# STM32_demo.net
KiCad netlist of a schematic drawn in Altium Designer
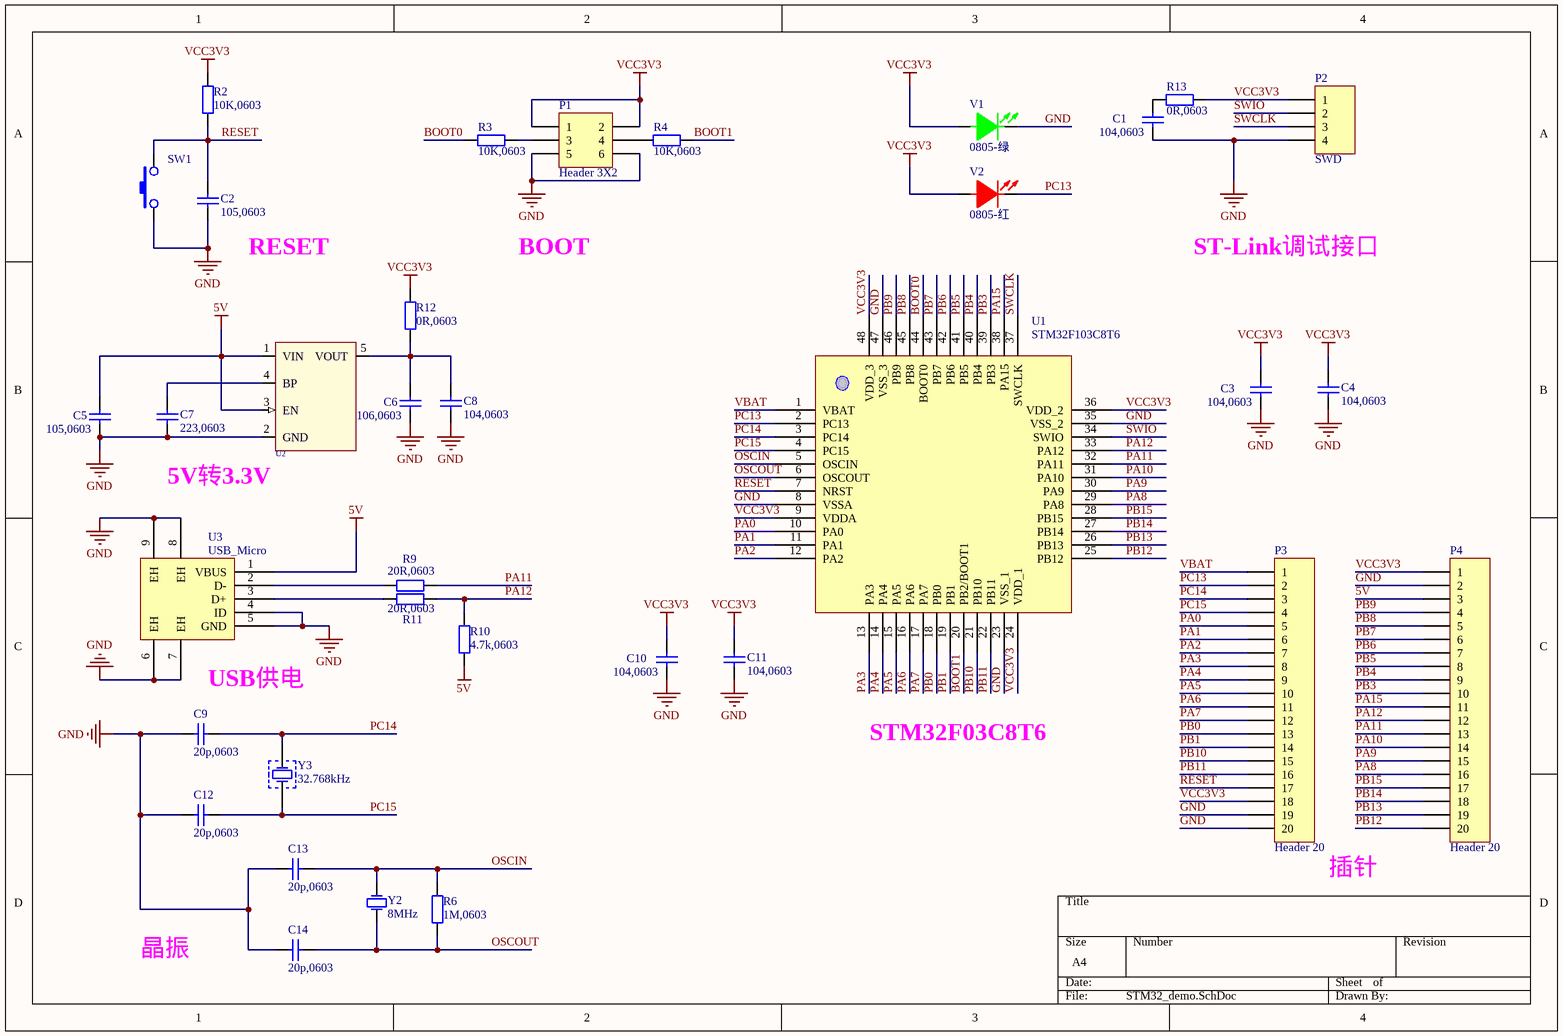
[diagram p0: STM32_demo.SchDoc]

(export (version "E")
  (design (tool "Eeschema 10.0.6"))
  (components
    (comp (ref "C1")
      (value "104,0603")
      (footprint "C0603")
      (description "Capacitor")
      (fields (field (name "PUBLISHER") "Altium Limited"))
      (libsource (lib "STM32F103C8T6") (part "Cap"))
    )
    (comp (ref "C2")
      (value "105,0603")
      (footprint "C0603")
      (description "Capacitor")
      (fields (field (name "PUBLISHER") "Altium Limited"))
      (libsource (lib "STM32F103C8T6") (part "Cap"))
    )
    (comp (ref "C3")
      (value "104,0603")
      (footprint "C0603")
      (description "Capacitor")
      (fields (field (name "PUBLISHER") "Altium Limited"))
      (libsource (lib "STM32F103C8T6") (part "Cap"))
    )
    (comp (ref "C4")
      (value "104,0603")
      (footprint "C0603")
      (description "Capacitor")
      (fields (field (name "PUBLISHER") "Altium Limited"))
      (libsource (lib "STM32F103C8T6") (part "Cap"))
    )
    (comp (ref "C5")
      (value "105,0603")
      (footprint "C0603")
      (description "Capacitor")
      (fields (field (name "PUBLISHER") "Altium Limited"))
      (libsource (lib "STM32F103C8T6") (part "Cap"))
    )
    (comp (ref "C6")
      (value "106,0603")
      (footprint "C0603")
      (description "Capacitor")
      (fields (field (name "PUBLISHER") "Altium Limited"))
      (libsource (lib "STM32F103C8T6") (part "Cap"))
    )
    (comp (ref "C7")
      (value "223,0603")
      (footprint "C0603")
      (description "Capacitor")
      (fields (field (name "PUBLISHER") "Altium Limited"))
      (libsource (lib "STM32F103C8T6") (part "Cap"))
    )
    (comp (ref "C8")
      (value "104,0603")
      (footprint "C0603")
      (description "Capacitor")
      (fields (field (name "PUBLISHER") "Altium Limited"))
      (libsource (lib "STM32F103C8T6") (part "Cap"))
    )
    (comp (ref "C9")
      (value "20p,0603")
      (footprint "C0603")
      (description "Capacitor")
      (fields (field (name "PUBLISHER") "Altium Limited"))
      (libsource (lib "STM32F103C8T6") (part "Cap"))
    )
    (comp (ref "C10")
      (value "104,0603")
      (footprint "C0603")
      (description "Capacitor")
      (fields (field (name "PUBLISHER") "Altium Limited"))
      (libsource (lib "STM32F103C8T6") (part "Cap"))
    )
    (comp (ref "C11")
      (value "104,0603")
      (footprint "C0603")
      (description "Capacitor")
      (fields (field (name "PUBLISHER") "Altium Limited"))
      (libsource (lib "STM32F103C8T6") (part "Cap"))
    )
    (comp (ref "C12")
      (value "20p,0603")
      (footprint "C0603")
      (description "Capacitor")
      (fields (field (name "PUBLISHER") "Altium Limited"))
      (libsource (lib "STM32F103C8T6") (part "Cap"))
    )
    (comp (ref "C13")
      (value "20p,0603")
      (footprint "C0603")
      (description "Capacitor")
      (fields (field (name "PUBLISHER") "Altium Limited"))
      (libsource (lib "STM32F103C8T6") (part "Cap"))
    )
    (comp (ref "C14")
      (value "20p,0603")
      (footprint "C0603")
      (description "Capacitor")
      (fields (field (name "PUBLISHER") "Altium Limited"))
      (libsource (lib "STM32F103C8T6") (part "Cap"))
    )
    (comp (ref "P1")
      (value "Header 3X2")
      (footprint "HDR2X3")
      (description "Header, 3-Pin, Dual row")
      (fields (field (name "PUBLISHER") "Altium Limited"))
      (libsource (lib "STM32F103C8T6") (part "Header 3X2"))
    )
    (comp (ref "P2")
      (value "SWD")
      (footprint "HDR1X4H")
      (description "Header, 4-Pin")
      (fields (field (name "PUBLISHER") "Altium Limited"))
      (libsource (lib "STM32F103C8T6") (part "Header 4"))
    )
    (comp (ref "P3")
      (value "Header 20")
      (footprint "HDR1X20")
      (description "Header, 20-Pin")
      (fields (field (name "PUBLISHER") "Altium Limited"))
      (libsource (lib "STM32F103C8T6") (part "Header 20"))
    )
    (comp (ref "P4")
      (value "Header 20")
      (footprint "HDR1X20")
      (description "Header, 20-Pin")
      (fields (field (name "PUBLISHER") "Altium Limited"))
      (libsource (lib "STM32F103C8T6") (part "Header 20"))
    )
    (comp (ref "R2")
      (value "10K,0603")
      (footprint "R0603")
      (description "Resistor")
      (fields (field (name "PUBLISHER") "Altium Limited"))
      (libsource (lib "") (part "Res2_2"))
    )
    (comp (ref "R3")
      (value "10K,0603")
      (footprint "R0603")
      (description "Resistor")
      (fields (field (name "PUBLISHER") "Altium Limited"))
      (libsource (lib "") (part "Res2_3"))
    )
    (comp (ref "R4")
      (value "10K,0603")
      (footprint "R0603")
      (description "Resistor")
      (fields (field (name "PUBLISHER") "Altium Limited"))
      (libsource (lib "") (part "Res2_3"))
    )
    (comp (ref "R6")
      (value "1M,0603")
      (footprint "R0603")
      (description "Resistor")
      (fields (field (name "PUBLISHER") "Altium Limited"))
      (libsource (lib "") (part "Res2_1"))
    )
    (comp (ref "R9")
      (value "20R,0603")
      (footprint "R0603")
      (description "Resistor")
      (fields (field (name "PUBLISHER") "Altium Limited"))
      (libsource (lib "STM32F103C8T6") (part "Res2"))
    )
    (comp (ref "R10")
      (value "4.7k,0603")
      (footprint "R0603")
      (description "Resistor")
      (fields (field (name "PUBLISHER") "Altium Limited"))
      (libsource (lib "") (part "Res2_1"))
    )
    (comp (ref "R11")
      (value "20R,0603")
      (footprint "R0603")
      (description "Resistor")
      (fields (field (name "PUBLISHER") "Altium Limited"))
      (libsource (lib "STM32F103C8T6") (part "Res2"))
    )
    (comp (ref "R12")
      (value "0R,0603")
      (footprint "R0603")
      (description "Resistor")
      (fields (field (name "PUBLISHER") "Altium Limited"))
      (libsource (lib "") (part "Res2_2"))
    )
    (comp (ref "R13")
      (value "0R,0603")
      (footprint "R0603")
      (description "Resistor")
      (fields (field (name "PUBLISHER") "Altium Limited"))
      (libsource (lib "STM32F103C8T6") (part "Res2"))
    )
    (comp (ref "SW1")
      (value "~")
      (footprint "KEY-SMT")
      (description "SWITCH")
      (libsource (lib "STM32F103C8T6") (part "SW-PB_V"))
    )
    (comp (ref "U1")
      (value "STM32F103C8T6")
      (footprint "48P")
      (libsource (lib "STM32F103C8T6") (part "STM32F103C8T6"))
    )
    (comp (ref "U2")
      (value "RT9193")
      (fields (field (name "ICA_PARTNUM") "$$2191094$$RT9193-15CU5") (field (name "PART NUMBER") "TMP-13"))
      (libsource (lib "STM32F103C8T6") (part "RT9193X_5P"))
    )
    (comp (ref "U3")
      (value "USB_Micro")
      (footprint "micro_usb_jlc")
      (libsource (lib "STM32F103C8T6") (part "micro_usb"))
    )
    (comp (ref "V1")
      (value "0805-绿")
      (footprint "LED0805-G")
      (description "WZYG0805-DTZ(绿/片式/70mcd)")
      (libsource (lib "WSDLIB-PLM") (part "LED-G"))
    )
    (comp (ref "V2")
      (value "0805-红")
      (footprint "LED0805-R")
      (description "FSL-R2210040HR-TNWSD(红/片式/112mcd)")
      (libsource (lib "WSDLIB-PLM") (part "LED-R"))
    )
    (comp (ref "Y2")
      (value "8MHz")
      (footprint "XTL-HC49S-SMD-2P")
      (description "20MHz-8pF-20ppm/HC49S-SMD/明德亨")
      (libsource (lib "WSDLIB-PLM") (part "Crystal-HC49S-2P"))
    )
    (comp (ref "Y3")
      (value "32.768kHz")
      (footprint "XTL-3215SMD")
      (description "32.768kHz-12.5pF-20ppm/XTL-3215/CITIZEN(国标RoHS、欧盟RoHS2.0、REACH)")
      (libsource (lib "WSDLIB-PLM") (part "Crystal-32768-2P"))
    )
  )
  (nets
    (net (code "1") (name "/BOOT0") (class "Default")
      (node (ref "R3") (pin "1") (pinfunction "1_1") (pintype "passive"))
      (node (ref "U1") (pin "44") (pinfunction "BOOT0_44") (pintype "passive"))
    )
    (net (code "2") (name "/BOOT1") (class "Default")
      (node (ref "R4") (pin "2") (pinfunction "2_2") (pintype "passive"))
      (node (ref "U1") (pin "20") (pinfunction "PB2/BOOT1_20") (pintype "passive"))
    )
    (net (code "3") (name "/OSCIN") (class "Default")
      (node (ref "C13") (pin "1") (pinfunction "1_1") (pintype "passive"))
      (node (ref "R6") (pin "1") (pinfunction "1_1") (pintype "passive"))
      (node (ref "U1") (pin "5") (pinfunction "OSCIN_5") (pintype "passive"))
      (node (ref "Y2") (pin "2") (pinfunction "OSC2_2") (pintype "passive"))
    )
    (net (code "4") (name "/OSCOUT") (class "Default")
      (node (ref "C14") (pin "1") (pinfunction "1_1") (pintype "passive"))
      (node (ref "R6") (pin "2") (pinfunction "2_2") (pintype "passive"))
      (node (ref "U1") (pin "6") (pinfunction "OSCOUT_6") (pintype "passive"))
      (node (ref "Y2") (pin "1") (pinfunction "OSC1_1") (pintype "passive"))
    )
    (net (code "5") (name "/PA0") (class "Default")
      (node (ref "P3") (pin "5") (pinfunction "5_5") (pintype "passive"))
      (node (ref "U1") (pin "10") (pinfunction "PA0_10") (pintype "passive"))
    )
    (net (code "6") (name "/PA1") (class "Default")
      (node (ref "P3") (pin "6") (pinfunction "6_6") (pintype "passive"))
      (node (ref "U1") (pin "11") (pinfunction "PA1_11") (pintype "passive"))
    )
    (net (code "7") (name "/PA2") (class "Default")
      (node (ref "P3") (pin "7") (pinfunction "7_7") (pintype "passive"))
      (node (ref "U1") (pin "12") (pinfunction "PA2_12") (pintype "passive"))
    )
    (net (code "8") (name "/PA3") (class "Default")
      (node (ref "P3") (pin "8") (pinfunction "8_8") (pintype "passive"))
      (node (ref "U1") (pin "13") (pinfunction "PA3_13") (pintype "passive"))
    )
    (net (code "9") (name "/PA4") (class "Default")
      (node (ref "P3") (pin "9") (pinfunction "9_9") (pintype "passive"))
      (node (ref "U1") (pin "14") (pinfunction "PA4_14") (pintype "passive"))
    )
    (net (code "10") (name "/PA5") (class "Default")
      (node (ref "P3") (pin "10") (pinfunction "10_10") (pintype "passive"))
      (node (ref "U1") (pin "15") (pinfunction "PA5_15") (pintype "passive"))
    )
    (net (code "11") (name "/PA6") (class "Default")
      (node (ref "P3") (pin "11") (pinfunction "11_11") (pintype "passive"))
      (node (ref "U1") (pin "16") (pinfunction "PA6_16") (pintype "passive"))
    )
    (net (code "12") (name "/PA7") (class "Default")
      (node (ref "P3") (pin "12") (pinfunction "12_12") (pintype "passive"))
      (node (ref "U1") (pin "17") (pinfunction "PA7_17") (pintype "passive"))
    )
    (net (code "13") (name "/PA8") (class "Default")
      (node (ref "P4") (pin "16") (pinfunction "16_16") (pintype "passive"))
      (node (ref "U1") (pin "29") (pinfunction "PA8_29") (pintype "passive"))
    )
    (net (code "14") (name "/PA9") (class "Default")
      (node (ref "P4") (pin "15") (pinfunction "15_15") (pintype "passive"))
      (node (ref "U1") (pin "30") (pinfunction "PA9_30") (pintype "passive"))
    )
    (net (code "15") (name "/PA10") (class "Default")
      (node (ref "P4") (pin "14") (pinfunction "14_14") (pintype "passive"))
      (node (ref "U1") (pin "31") (pinfunction "PA10_31") (pintype "passive"))
    )
    (net (code "16") (name "/PA11") (class "Default")
      (node (ref "P4") (pin "13") (pinfunction "13_13") (pintype "passive"))
      (node (ref "R9") (pin "1") (pinfunction "1_1") (pintype "passive"))
      (node (ref "U1") (pin "32") (pinfunction "PA11_32") (pintype "passive"))
    )
    (net (code "17") (name "/PA12") (class "Default")
      (node (ref "P4") (pin "12") (pinfunction "12_12") (pintype "passive"))
      (node (ref "R10") (pin "1") (pinfunction "1_1") (pintype "passive"))
      (node (ref "R11") (pin "1") (pinfunction "1_1") (pintype "passive"))
      (node (ref "U1") (pin "33") (pinfunction "PA12_33") (pintype "passive"))
    )
    (net (code "18") (name "/PA15") (class "Default")
      (node (ref "P4") (pin "11") (pinfunction "11_11") (pintype "passive"))
      (node (ref "U1") (pin "38") (pinfunction "PA15_38") (pintype "passive"))
    )
    (net (code "19") (name "/PB0") (class "Default")
      (node (ref "P3") (pin "13") (pinfunction "13_13") (pintype "passive"))
      (node (ref "U1") (pin "18") (pinfunction "PB0_18") (pintype "passive"))
    )
    (net (code "20") (name "/PB1") (class "Default")
      (node (ref "P3") (pin "14") (pinfunction "14_14") (pintype "passive"))
      (node (ref "U1") (pin "19") (pinfunction "PB1_19") (pintype "passive"))
    )
    (net (code "21") (name "/PB3") (class "Default")
      (node (ref "P4") (pin "10") (pinfunction "10_10") (pintype "passive"))
      (node (ref "U1") (pin "39") (pinfunction "PB3_39") (pintype "passive"))
    )
    (net (code "22") (name "/PB4") (class "Default")
      (node (ref "P4") (pin "9") (pinfunction "9_9") (pintype "passive"))
      (node (ref "U1") (pin "40") (pinfunction "PB4_40") (pintype "passive"))
    )
    (net (code "23") (name "/PB5") (class "Default")
      (node (ref "P4") (pin "8") (pinfunction "8_8") (pintype "passive"))
      (node (ref "U1") (pin "41") (pinfunction "PB5_41") (pintype "passive"))
    )
    (net (code "24") (name "/PB6") (class "Default")
      (node (ref "P4") (pin "7") (pinfunction "7_7") (pintype "passive"))
      (node (ref "U1") (pin "42") (pinfunction "PB6_42") (pintype "passive"))
    )
    (net (code "25") (name "/PB7") (class "Default")
      (node (ref "P4") (pin "6") (pinfunction "6_6") (pintype "passive"))
      (node (ref "U1") (pin "43") (pinfunction "PB7_43") (pintype "passive"))
    )
    (net (code "26") (name "/PB8") (class "Default")
      (node (ref "P4") (pin "5") (pinfunction "5_5") (pintype "passive"))
      (node (ref "U1") (pin "45") (pinfunction "PB8_45") (pintype "passive"))
    )
    (net (code "27") (name "/PB9") (class "Default")
      (node (ref "P4") (pin "4") (pinfunction "4_4") (pintype "passive"))
      (node (ref "U1") (pin "46") (pinfunction "PB9_46") (pintype "passive"))
    )
    (net (code "28") (name "/PB10") (class "Default")
      (node (ref "P3") (pin "15") (pinfunction "15_15") (pintype "passive"))
      (node (ref "U1") (pin "21") (pinfunction "PB10_21") (pintype "passive"))
    )
    (net (code "29") (name "/PB11") (class "Default")
      (node (ref "P3") (pin "16") (pinfunction "16_16") (pintype "passive"))
      (node (ref "U1") (pin "22") (pinfunction "PB11_22") (pintype "passive"))
    )
    (net (code "30") (name "/PB12") (class "Default")
      (node (ref "P4") (pin "20") (pinfunction "20_20") (pintype "passive"))
      (node (ref "U1") (pin "25") (pinfunction "PB12_25") (pintype "passive"))
    )
    (net (code "31") (name "/PB13") (class "Default")
      (node (ref "P4") (pin "19") (pinfunction "19_19") (pintype "passive"))
      (node (ref "U1") (pin "26") (pinfunction "PB13_26") (pintype "passive"))
    )
    (net (code "32") (name "/PB14") (class "Default")
      (node (ref "P4") (pin "18") (pinfunction "18_18") (pintype "passive"))
      (node (ref "U1") (pin "27") (pinfunction "PB14_27") (pintype "passive"))
    )
    (net (code "33") (name "/PB15") (class "Default")
      (node (ref "P4") (pin "17") (pinfunction "17_17") (pintype "passive"))
      (node (ref "U1") (pin "28") (pinfunction "PB15_28") (pintype "passive"))
    )
    (net (code "34") (name "/PC13") (class "Default")
      (node (ref "P3") (pin "2") (pinfunction "2_2") (pintype "passive"))
      (node (ref "U1") (pin "2") (pinfunction "PC13_2") (pintype "passive"))
      (node (ref "V2") (pin "K") (pinfunction "2_K") (pintype "passive"))
    )
    (net (code "35") (name "/PC14") (class "Default")
      (node (ref "C9") (pin "1") (pinfunction "1_1") (pintype "passive"))
      (node (ref "P3") (pin "3") (pinfunction "3_3") (pintype "passive"))
      (node (ref "U1") (pin "3") (pinfunction "PC14_3") (pintype "passive"))
      (node (ref "Y3") (pin "2") (pinfunction "OSC2_2") (pintype "passive"))
    )
    (net (code "36") (name "/PC15") (class "Default")
      (node (ref "C12") (pin "1") (pinfunction "1_1") (pintype "passive"))
      (node (ref "P3") (pin "4") (pinfunction "4_4") (pintype "passive"))
      (node (ref "U1") (pin "4") (pinfunction "PC15_4") (pintype "passive"))
      (node (ref "Y3") (pin "1") (pinfunction "OSC1_1") (pintype "passive"))
    )
    (net (code "37") (name "/RESET") (class "Default")
      (node (ref "C2") (pin "2") (pinfunction "2_2") (pintype "passive"))
      (node (ref "P3") (pin "17") (pinfunction "17_17") (pintype "passive"))
      (node (ref "R2") (pin "1") (pinfunction "1_1") (pintype "passive"))
      (node (ref "SW1") (pin "2") (pinfunction "2_2") (pintype "passive"))
      (node (ref "U1") (pin "7") (pinfunction "NRST_7") (pintype "passive"))
    )
    (net (code "38") (name "/SWCLK") (class "Default")
      (node (ref "P2") (pin "3") (pinfunction "3_3") (pintype "passive"))
      (node (ref "U1") (pin "37") (pinfunction "SWCLK_37") (pintype "passive"))
    )
    (net (code "39") (name "/SWIO") (class "Default")
      (node (ref "P2") (pin "2") (pinfunction "2_2") (pintype "passive"))
      (node (ref "U1") (pin "34") (pinfunction "SWIO_34") (pintype "passive"))
    )
    (net (code "40") (name "/VBAT") (class "Default")
      (node (ref "P3") (pin "1") (pinfunction "1_1") (pintype "passive"))
      (node (ref "U1") (pin "1") (pinfunction "VBAT_1") (pintype "passive"))
    )
    (net (code "41") (name "5V") (class "Default")
      (node (ref "C5") (pin "2") (pinfunction "2_2") (pintype "passive"))
      (node (ref "P4") (pin "3") (pinfunction "3_3") (pintype "passive"))
      (node (ref "R10") (pin "2") (pinfunction "2_2") (pintype "passive"))
      (node (ref "U2") (pin "1") (pinfunction "VIN_1") (pintype "power_in"))
      (node (ref "U2") (pin "3") (pinfunction "EN_3") (pintype "input"))
      (node (ref "U3") (pin "1") (pinfunction "VBUS_1") (pintype "passive"))
    )
    (net (code "42") (name "GND") (class "Default")
      (node (ref "C1") (pin "1") (pinfunction "1_1") (pintype "passive"))
      (node (ref "C10") (pin "1") (pinfunction "1_1") (pintype "passive"))
      (node (ref "C11") (pin "1") (pinfunction "1_1") (pintype "passive"))
      (node (ref "C12") (pin "2") (pinfunction "2_2") (pintype "passive"))
      (node (ref "C13") (pin "2") (pinfunction "2_2") (pintype "passive"))
      (node (ref "C14") (pin "2") (pinfunction "2_2") (pintype "passive"))
      (node (ref "C2") (pin "1") (pinfunction "1_1") (pintype "passive"))
      (node (ref "C3") (pin "1") (pinfunction "1_1") (pintype "passive"))
      (node (ref "C4") (pin "1") (pinfunction "1_1") (pintype "passive"))
      (node (ref "C5") (pin "1") (pinfunction "1_1") (pintype "passive"))
      (node (ref "C6") (pin "1") (pinfunction "1_1") (pintype "passive"))
      (node (ref "C7") (pin "1") (pinfunction "1_1") (pintype "passive"))
      (node (ref "C8") (pin "1") (pinfunction "1_1") (pintype "passive"))
      (node (ref "C9") (pin "2") (pinfunction "2_2") (pintype "passive"))
      (node (ref "P1") (pin "5") (pinfunction "5_5") (pintype "passive"))
      (node (ref "P1") (pin "6") (pinfunction "6_6") (pintype "passive"))
      (node (ref "P2") (pin "4") (pinfunction "4_4") (pintype "passive"))
      (node (ref "P3") (pin "19") (pinfunction "19_19") (pintype "passive"))
      (node (ref "P3") (pin "20") (pinfunction "20_20") (pintype "passive"))
      (node (ref "P4") (pin "2") (pinfunction "2_2") (pintype "passive"))
      (node (ref "SW1") (pin "1") (pinfunction "1_1") (pintype "passive"))
      (node (ref "U1") (pin "23") (pinfunction "VSS_1_23") (pintype "passive"))
      (node (ref "U1") (pin "35") (pinfunction "VSS_2_35") (pintype "passive"))
      (node (ref "U1") (pin "47") (pinfunction "VSS_3_47") (pintype "passive"))
      (node (ref "U1") (pin "8") (pinfunction "VSSA_8") (pintype "passive"))
      (node (ref "U2") (pin "2") (pinfunction "GND_2") (pintype "power_in"))
      (node (ref "U3") (pin "4") (pinfunction "ID_4") (pintype "passive"))
      (node (ref "U3") (pin "5") (pinfunction "GND_5") (pintype "passive"))
      (node (ref "U3") (pin "6") (pinfunction "EH_6") (pintype "passive"))
      (node (ref "U3") (pin "7") (pinfunction "EH_7") (pintype "passive"))
      (node (ref "U3") (pin "8") (pinfunction "EH_8") (pintype "passive"))
      (node (ref "U3") (pin "9") (pinfunction "EH_9") (pintype "passive"))
      (node (ref "V1") (pin "K") (pinfunction "2_K") (pintype "passive"))
    )
    (net (code "43") (name "Net-(C1-Pad2)") (class "Default")
      (node (ref "C1") (pin "2") (pinfunction "2_2") (pintype "passive"))
      (node (ref "R13") (pin "2") (pinfunction "2_2") (pintype "passive"))
    )
    (net (code "44") (name "Net-(P1-Pad3)") (class "Default")
      (node (ref "P1") (pin "3") (pinfunction "3_3") (pintype "passive"))
      (node (ref "R3") (pin "2") (pinfunction "2_2") (pintype "passive"))
    )
    (net (code "45") (name "Net-(P1-Pad4)") (class "Default")
      (node (ref "P1") (pin "4") (pinfunction "4_4") (pintype "passive"))
      (node (ref "R4") (pin "1") (pinfunction "1_1") (pintype "passive"))
    )
    (net (code "46") (name "Net-(U2-BP)") (class "Default")
      (node (ref "C7") (pin "2") (pinfunction "2_2") (pintype "passive"))
      (node (ref "U2") (pin "4") (pinfunction "BP_4") (pintype "passive"))
    )
    (net (code "47") (name "Net-(U2-VOUT)") (class "Default")
      (node (ref "C6") (pin "2") (pinfunction "2_2") (pintype "passive"))
      (node (ref "C8") (pin "2") (pinfunction "2_2") (pintype "passive"))
      (node (ref "R12") (pin "1") (pinfunction "1_1") (pintype "passive"))
      (node (ref "U2") (pin "5") (pinfunction "VOUT_5") (pintype "power_in"))
    )
    (net (code "48") (name "Net-(U3-D+)") (class "Default")
      (node (ref "R11") (pin "2") (pinfunction "2_2") (pintype "passive"))
      (node (ref "U3") (pin "3") (pinfunction "D+_3") (pintype "passive"))
    )
    (net (code "49") (name "Net-(U3-D-)") (class "Default")
      (node (ref "R9") (pin "2") (pinfunction "2_2") (pintype "passive"))
      (node (ref "U3") (pin "2") (pinfunction "D-_2") (pintype "passive"))
    )
    (net (code "50") (name "VCC3V3") (class "Default")
      (node (ref "C10") (pin "2") (pinfunction "2_2") (pintype "passive"))
      (node (ref "C11") (pin "2") (pinfunction "2_2") (pintype "passive"))
      (node (ref "C3") (pin "2") (pinfunction "2_2") (pintype "passive"))
      (node (ref "C4") (pin "2") (pinfunction "2_2") (pintype "passive"))
      (node (ref "P1") (pin "1") (pinfunction "1_1") (pintype "passive"))
      (node (ref "P1") (pin "2") (pinfunction "2_2") (pintype "passive"))
      (node (ref "P2") (pin "1") (pinfunction "1_1") (pintype "passive"))
      (node (ref "P3") (pin "18") (pinfunction "18_18") (pintype "passive"))
      (node (ref "P4") (pin "1") (pinfunction "1_1") (pintype "passive"))
      (node (ref "R12") (pin "2") (pinfunction "2_2") (pintype "passive"))
      (node (ref "R13") (pin "1") (pinfunction "1_1") (pintype "passive"))
      (node (ref "R2") (pin "2") (pinfunction "2_2") (pintype "passive"))
      (node (ref "U1") (pin "24") (pinfunction "VDD_1_24") (pintype "passive"))
      (node (ref "U1") (pin "36") (pinfunction "VDD_2_36") (pintype "passive"))
      (node (ref "U1") (pin "48") (pinfunction "VDD_3_48") (pintype "passive"))
      (node (ref "U1") (pin "9") (pinfunction "VDDA_9") (pintype "passive"))
      (node (ref "V1") (pin "A") (pinfunction "1_A") (pintype "passive"))
      (node (ref "V2") (pin "A") (pinfunction "1_A") (pintype "passive"))
    )
  )
)
